# battery_interface.net
KiCad netlist of a schematic drawn in Altium Designer
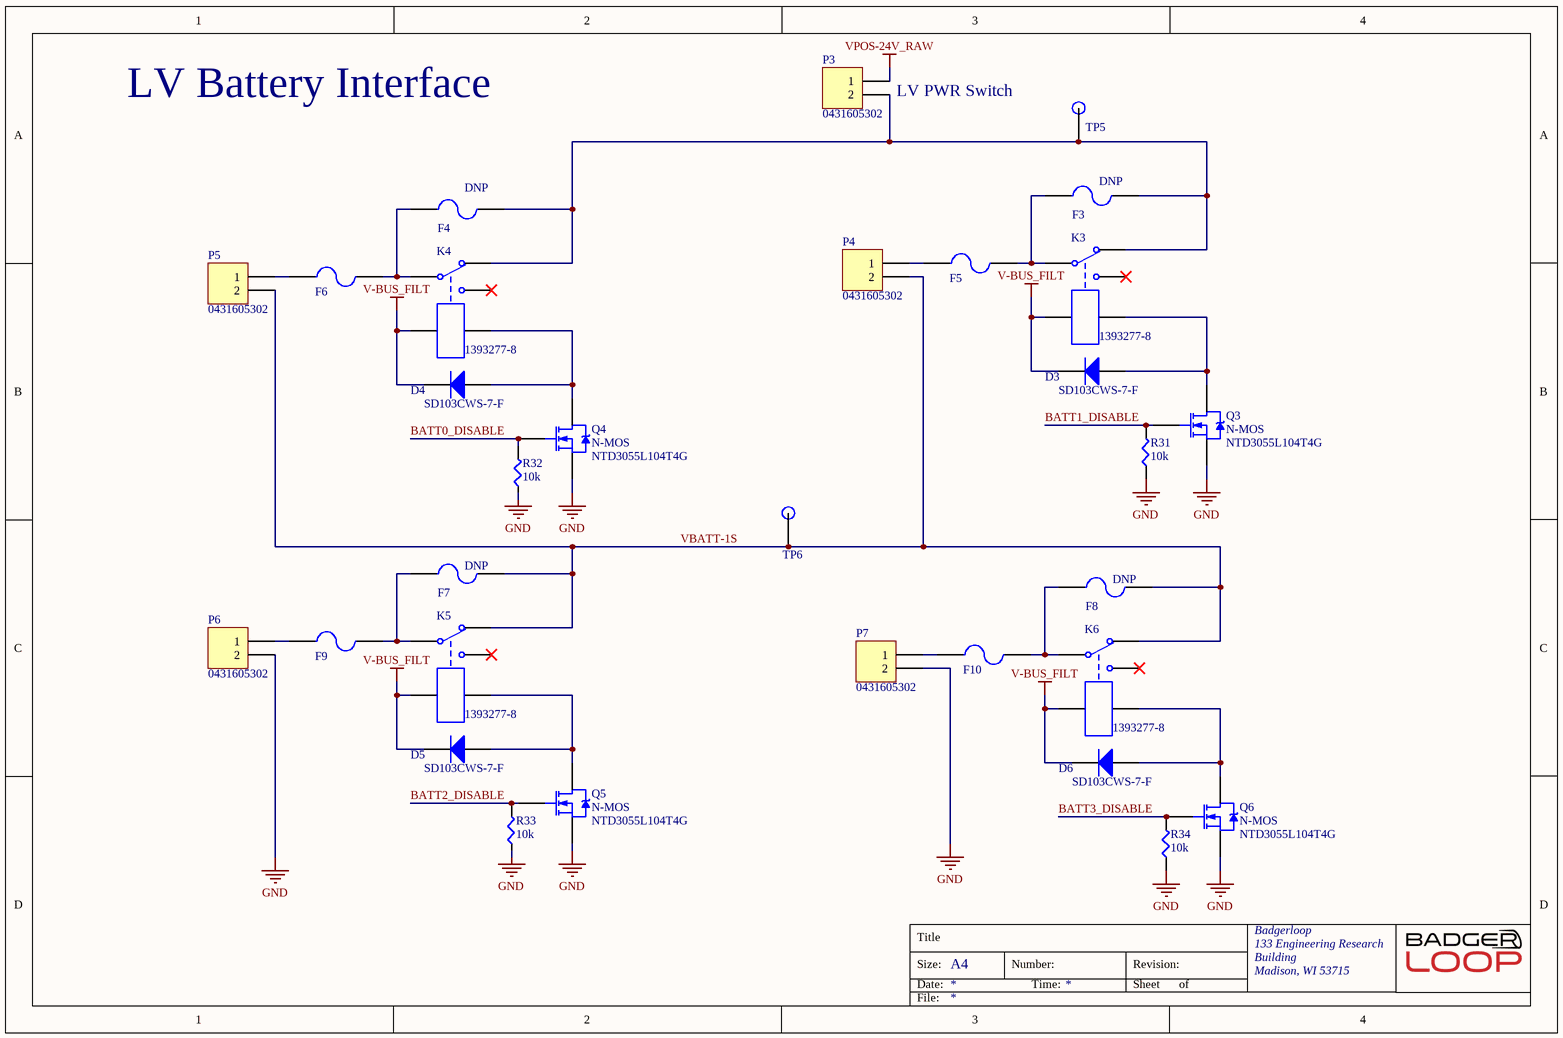
[diagram p0: battery_interface.SchDoc]

(export (version "E")
  (design (tool "Eeschema 10.0.6"))
  (components
    (comp (ref "D3")
      (value "Diode General Purpose_2")
      (footprint "SODFL250X110-2N")
      (description "DIODE GEN PURP 20V 350MA SOD323")
      (fields
        (field (name "MANUFACTURER") "Diodes Incorporated")
        (field (name "MANUFACTURER P/N") "SD103CWS-7-F")
      )
      (libsource (lib "misc") (part "Diode General Purpose_2"))
    )
    (comp (ref "D4")
      (value "Diode General Purpose_2")
      (footprint "SODFL250X110-2N")
      (description "DIODE GEN PURP 20V 350MA SOD323")
      (fields
        (field (name "MANUFACTURER") "Diodes Incorporated")
        (field (name "MANUFACTURER P/N") "SD103CWS-7-F")
      )
      (libsource (lib "misc") (part "Diode General Purpose_2"))
    )
    (comp (ref "D5")
      (value "Diode General Purpose_2")
      (footprint "SODFL250X110-2N")
      (description "DIODE GEN PURP 20V 350MA SOD323")
      (fields
        (field (name "MANUFACTURER") "Diodes Incorporated")
        (field (name "MANUFACTURER P/N") "SD103CWS-7-F")
      )
      (libsource (lib "misc") (part "Diode General Purpose_2"))
    )
    (comp (ref "D6")
      (value "Diode General Purpose_2")
      (footprint "SODFL250X110-2N")
      (description "DIODE GEN PURP 20V 350MA SOD323")
      (fields
        (field (name "MANUFACTURER") "Diodes Incorporated")
        (field (name "MANUFACTURER P/N") "SD103CWS-7-F")
      )
      (libsource (lib "misc") (part "Diode General Purpose_2"))
    )
    (comp (ref "F3")
      (value "3568")
      (footprint "Fuse Holder 30A 500V 1 Circuit Blade Through Hole")
      (description "FUSE HOLDER MINI AUTO PC")
      (fields
        (field (name "MANUFACTURER") "Keystone Electronics")
        (field (name "VOLTAGE") "500V")
        (field (name "DNP") "DNP")
      )
      (libsource (lib "misc") (part "3568"))
    )
    (comp (ref "F4")
      (value "3568")
      (footprint "Fuse Holder 30A 500V 1 Circuit Blade Through Hole")
      (description "FUSE HOLDER MINI AUTO PC")
      (fields
        (field (name "MANUFACTURER") "Keystone Electronics")
        (field (name "VOLTAGE") "500V")
        (field (name "DNP") "DNP")
      )
      (libsource (lib "misc") (part "3568"))
    )
    (comp (ref "F5")
      (value "3568")
      (footprint "Fuse Holder 30A 500V 1 Circuit Blade Through Hole")
      (description "FUSE HOLDER MINI AUTO PC")
      (fields (field (name "MANUFACTURER") "Keystone Electronics") (field (name "VOLTAGE") "500V"))
      (libsource (lib "misc") (part "3568"))
    )
    (comp (ref "F6")
      (value "3568")
      (footprint "Fuse Holder 30A 500V 1 Circuit Blade Through Hole")
      (description "FUSE HOLDER MINI AUTO PC")
      (fields (field (name "MANUFACTURER") "Keystone Electronics") (field (name "VOLTAGE") "500V"))
      (libsource (lib "misc") (part "3568"))
    )
    (comp (ref "F7")
      (value "3568")
      (footprint "Fuse Holder 30A 500V 1 Circuit Blade Through Hole")
      (description "FUSE HOLDER MINI AUTO PC")
      (fields
        (field (name "MANUFACTURER") "Keystone Electronics")
        (field (name "VOLTAGE") "500V")
        (field (name "DNP") "DNP")
      )
      (libsource (lib "misc") (part "3568"))
    )
    (comp (ref "F8")
      (value "3568")
      (footprint "Fuse Holder 30A 500V 1 Circuit Blade Through Hole")
      (description "FUSE HOLDER MINI AUTO PC")
      (fields
        (field (name "MANUFACTURER") "Keystone Electronics")
        (field (name "VOLTAGE") "500V")
        (field (name "DNP") "DNP")
      )
      (libsource (lib "misc") (part "3568"))
    )
    (comp (ref "F9")
      (value "3568")
      (footprint "Fuse Holder 30A 500V 1 Circuit Blade Through Hole")
      (description "FUSE HOLDER MINI AUTO PC")
      (fields (field (name "MANUFACTURER") "Keystone Electronics") (field (name "VOLTAGE") "500V"))
      (libsource (lib "misc") (part "3568"))
    )
    (comp (ref "F10")
      (value "3568")
      (footprint "Fuse Holder 30A 500V 1 Circuit Blade Through Hole")
      (description "FUSE HOLDER MINI AUTO PC")
      (fields (field (name "MANUFACTURER") "Keystone Electronics") (field (name "VOLTAGE") "500V"))
      (libsource (lib "misc") (part "3568"))
    )
    (comp (ref "K3")
      (value "1393277-8")
      (footprint "RELAY AUTOMOTIVE SPDT 45A 24V - duplicate")
      (description "RELAY AUTOMOTIVE SPDT 45A 24V")
      (fields (field (name "MANUFACTURER") "TE Connectivity"))
      (libsource (lib "misc") (part "1393277-8"))
    )
    (comp (ref "K4")
      (value "1393277-8")
      (footprint "RELAY AUTOMOTIVE SPDT 45A 24V - duplicate")
      (description "RELAY AUTOMOTIVE SPDT 45A 24V")
      (fields (field (name "MANUFACTURER") "TE Connectivity"))
      (libsource (lib "misc") (part "1393277-8"))
    )
    (comp (ref "K5")
      (value "1393277-8")
      (footprint "RELAY AUTOMOTIVE SPDT 45A 24V - duplicate")
      (description "RELAY AUTOMOTIVE SPDT 45A 24V")
      (fields (field (name "MANUFACTURER") "TE Connectivity"))
      (libsource (lib "misc") (part "1393277-8"))
    )
    (comp (ref "K6")
      (value "1393277-8")
      (footprint "RELAY AUTOMOTIVE SPDT 45A 24V - duplicate")
      (description "RELAY AUTOMOTIVE SPDT 45A 24V")
      (fields (field (name "MANUFACTURER") "TE Connectivity"))
      (libsource (lib "misc") (part "1393277-8"))
    )
    (comp (ref "P3")
      (value "0431605302")
      (footprint "CONN HDR 2POS 7.50MM")
      (description "Conn Power HDR 2 POS 7.49mm Solder RA Thru-Hole 4 Terminal 1 Port Sabre™ Tray")
      (fields (field (name "MANUFACTURER") "Molex"))
      (libsource (lib "connector") (part "0431605302"))
    )
    (comp (ref "P4")
      (value "0431605302")
      (footprint "CONN HDR 2POS 7.50MM")
      (description "Conn Power HDR 2 POS 7.49mm Solder RA Thru-Hole 4 Terminal 1 Port Sabre™ Tray")
      (fields (field (name "MANUFACTURER") "Molex"))
      (libsource (lib "connector") (part "0431605302"))
    )
    (comp (ref "P5")
      (value "0431605302")
      (footprint "CONN HDR 2POS 7.50MM")
      (description "Conn Power HDR 2 POS 7.49mm Solder RA Thru-Hole 4 Terminal 1 Port Sabre™ Tray")
      (fields (field (name "MANUFACTURER") "Molex"))
      (libsource (lib "connector") (part "0431605302"))
    )
    (comp (ref "P6")
      (value "0431605302")
      (footprint "CONN HDR 2POS 7.50MM")
      (description "Conn Power HDR 2 POS 7.49mm Solder RA Thru-Hole 4 Terminal 1 Port Sabre™ Tray")
      (fields (field (name "MANUFACTURER") "Molex"))
      (libsource (lib "connector") (part "0431605302"))
    )
    (comp (ref "P7")
      (value "0431605302")
      (footprint "CONN HDR 2POS 7.50MM")
      (description "Conn Power HDR 2 POS 7.49mm Solder RA Thru-Hole 4 Terminal 1 Port Sabre™ Tray")
      (fields (field (name "MANUFACTURER") "Molex"))
      (libsource (lib "connector") (part "0431605302"))
    )
    (comp (ref "Q3")
      (value "N-MOS")
      (footprint "DPAK228P991X238-3N")
      (description "N-Channel Power MOSFET, 12 A, 60 V")
      (fields (field (name "MANUFACTURER") "ON SEMI") (field (name "MANUFACTURER P/N") "NTD3055L104T4G"))
      (libsource (lib "ic") (part "N-MOS"))
    )
    (comp (ref "Q4")
      (value "N-MOS")
      (footprint "DPAK228P991X238-3N")
      (description "N-Channel Power MOSFET, 12 A, 60 V")
      (fields (field (name "MANUFACTURER") "ON SEMI") (field (name "MANUFACTURER P/N") "NTD3055L104T4G"))
      (libsource (lib "ic") (part "N-MOS"))
    )
    (comp (ref "Q5")
      (value "N-MOS")
      (footprint "DPAK228P991X238-3N")
      (description "N-Channel Power MOSFET, 12 A, 60 V")
      (fields (field (name "MANUFACTURER") "ON SEMI") (field (name "MANUFACTURER P/N") "NTD3055L104T4G"))
      (libsource (lib "ic") (part "N-MOS"))
    )
    (comp (ref "Q6")
      (value "N-MOS")
      (footprint "DPAK228P991X238-3N")
      (description "N-Channel Power MOSFET, 12 A, 60 V")
      (fields (field (name "MANUFACTURER") "ON SEMI") (field (name "MANUFACTURER P/N") "NTD3055L104T4G"))
      (libsource (lib "ic") (part "N-MOS"))
    )
    (comp (ref "R31")
      (value "10k")
      (footprint "SMD-0805-RES")
      (description "RES SMD 10K OHM 5% 1/2W 0805")
      (fields (field (name "PART NUMBER") "ERJ-P06J103V") (field (name "DIGI-KEY PART NUMBER") "P10KADCT-ND"))
      (libsource (lib "resistors") (part "ERJ-P06J103V"))
    )
    (comp (ref "R32")
      (value "10k")
      (footprint "SMD-0805-RES")
      (description "RES SMD 10K OHM 5% 1/2W 0805")
      (fields (field (name "PART NUMBER") "ERJ-P06J103V") (field (name "DIGI-KEY PART NUMBER") "P10KADCT-ND"))
      (libsource (lib "resistors") (part "ERJ-P06J103V"))
    )
    (comp (ref "R33")
      (value "10k")
      (footprint "SMD-0805-RES")
      (description "RES SMD 10K OHM 5% 1/2W 0805")
      (fields (field (name "PART NUMBER") "ERJ-P06J103V") (field (name "DIGI-KEY PART NUMBER") "P10KADCT-ND"))
      (libsource (lib "resistors") (part "ERJ-P06J103V"))
    )
    (comp (ref "R34")
      (value "10k")
      (footprint "SMD-0805-RES")
      (description "RES SMD 10K OHM 5% 1/2W 0805")
      (fields (field (name "PART NUMBER") "ERJ-P06J103V") (field (name "DIGI-KEY PART NUMBER") "P10KADCT-ND"))
      (libsource (lib "resistors") (part "ERJ-P06J103V"))
    )
    (comp (ref "TP5")
      (value "TP")
      (footprint "Test Point")
      (description "SMD TEST POINT")
      (libsource (lib "misc") (part "TP"))
    )
    (comp (ref "TP6")
      (value "TP")
      (footprint "Test Point")
      (description "SMD TEST POINT")
      (libsource (lib "misc") (part "TP"))
    )
  )
  (nets
    (net (code "1") (name "/BATT0_DISABLE") (class "Default")
      (node (ref "Q4") (pin "1") (pinfunction "G_1") (pintype "passive"))
      (node (ref "R32") (pin "2") (pinfunction "2_2") (pintype "passive"))
    )
    (net (code "2") (name "/BATT1_DISABLE") (class "Default")
      (node (ref "Q3") (pin "1") (pinfunction "G_1") (pintype "passive"))
      (node (ref "R31") (pin "2") (pinfunction "2_2") (pintype "passive"))
    )
    (net (code "3") (name "/BATT2_DISABLE") (class "Default")
      (node (ref "Q5") (pin "1") (pinfunction "G_1") (pintype "passive"))
      (node (ref "R33") (pin "2") (pinfunction "2_2") (pintype "passive"))
    )
    (net (code "4") (name "/BATT3_DISABLE") (class "Default")
      (node (ref "Q6") (pin "1") (pinfunction "G_1") (pintype "passive"))
      (node (ref "R34") (pin "2") (pinfunction "2_2") (pintype "passive"))
    )
    (net (code "5") (name "/VBATT-1S") (class "Default")
      (node (ref "F7") (pin "2") (pinfunction "2_2") (pintype "passive"))
      (node (ref "F8") (pin "2") (pinfunction "2_2") (pintype "passive"))
      (node (ref "K5") (pin "3") (pinfunction "3_3") (pintype "passive"))
      (node (ref "K6") (pin "3") (pinfunction "3_3") (pintype "passive"))
      (node (ref "P4") (pin "2") (pinfunction "2_2") (pintype "passive"))
      (node (ref "P5") (pin "2") (pinfunction "2_2") (pintype "passive"))
      (node (ref "TP6") (pin "1") (pinfunction "1_1") (pintype "passive"))
    )
    (net (code "6") (name "GND") (class "Default")
      (node (ref "P6") (pin "2") (pinfunction "2_2") (pintype "passive"))
      (node (ref "P7") (pin "2") (pinfunction "2_2") (pintype "passive"))
      (node (ref "Q3") (pin "3") (pinfunction "S_3") (pintype "passive"))
      (node (ref "Q4") (pin "3") (pinfunction "S_3") (pintype "passive"))
      (node (ref "Q5") (pin "3") (pinfunction "S_3") (pintype "passive"))
      (node (ref "Q6") (pin "3") (pinfunction "S_3") (pintype "passive"))
      (node (ref "R31") (pin "1") (pinfunction "1_1") (pintype "passive"))
      (node (ref "R32") (pin "1") (pinfunction "1_1") (pintype "passive"))
      (node (ref "R33") (pin "1") (pinfunction "1_1") (pintype "passive"))
      (node (ref "R34") (pin "1") (pinfunction "1_1") (pintype "passive"))
    )
    (net (code "7") (name "Net-(D3-A)") (class "Default")
      (node (ref "D3") (pin "1") (pinfunction "A_1") (pintype "passive"))
      (node (ref "K3") (pin "2") (pinfunction "2_2") (pintype "passive"))
      (node (ref "Q3") (pin "4") (pinfunction "D_4") (pintype "passive"))
    )
    (net (code "8") (name "Net-(D4-A)") (class "Default")
      (node (ref "D4") (pin "1") (pinfunction "A_1") (pintype "passive"))
      (node (ref "K4") (pin "2") (pinfunction "2_2") (pintype "passive"))
      (node (ref "Q4") (pin "4") (pinfunction "D_4") (pintype "passive"))
    )
    (net (code "9") (name "Net-(D5-A)") (class "Default")
      (node (ref "D5") (pin "1") (pinfunction "A_1") (pintype "passive"))
      (node (ref "K5") (pin "2") (pinfunction "2_2") (pintype "passive"))
      (node (ref "Q5") (pin "4") (pinfunction "D_4") (pintype "passive"))
    )
    (net (code "10") (name "Net-(D6-A)") (class "Default")
      (node (ref "D6") (pin "1") (pinfunction "A_1") (pintype "passive"))
      (node (ref "K6") (pin "2") (pinfunction "2_2") (pintype "passive"))
      (node (ref "Q6") (pin "4") (pinfunction "D_4") (pintype "passive"))
    )
    (net (code "11") (name "Net-(F3-Pad1)") (class "Default")
      (node (ref "F3") (pin "1") (pinfunction "1_1") (pintype "passive"))
      (node (ref "F5") (pin "2") (pinfunction "2_2") (pintype "passive"))
      (node (ref "K3") (pin "4") (pinfunction "4_4") (pintype "passive"))
    )
    (net (code "12") (name "Net-(F3-Pad2)") (class "Default")
      (node (ref "F3") (pin "2") (pinfunction "2_2") (pintype "passive"))
      (node (ref "F4") (pin "2") (pinfunction "2_2") (pintype "passive"))
      (node (ref "K3") (pin "3") (pinfunction "3_3") (pintype "passive"))
      (node (ref "K4") (pin "3") (pinfunction "3_3") (pintype "passive"))
      (node (ref "P3") (pin "2") (pinfunction "2_2") (pintype "passive"))
      (node (ref "TP5") (pin "1") (pinfunction "1_1") (pintype "passive"))
    )
    (net (code "13") (name "Net-(F4-Pad1)") (class "Default")
      (node (ref "F4") (pin "1") (pinfunction "1_1") (pintype "passive"))
      (node (ref "F6") (pin "2") (pinfunction "2_2") (pintype "passive"))
      (node (ref "K4") (pin "4") (pinfunction "4_4") (pintype "passive"))
    )
    (net (code "14") (name "Net-(F5-Pad1)") (class "Default")
      (node (ref "F5") (pin "1") (pinfunction "1_1") (pintype "passive"))
      (node (ref "P4") (pin "1") (pinfunction "1_1") (pintype "passive"))
    )
    (net (code "15") (name "Net-(F6-Pad1)") (class "Default")
      (node (ref "F6") (pin "1") (pinfunction "1_1") (pintype "passive"))
      (node (ref "P5") (pin "1") (pinfunction "1_1") (pintype "passive"))
    )
    (net (code "16") (name "Net-(F7-Pad1)") (class "Default")
      (node (ref "F7") (pin "1") (pinfunction "1_1") (pintype "passive"))
      (node (ref "F9") (pin "2") (pinfunction "2_2") (pintype "passive"))
      (node (ref "K5") (pin "4") (pinfunction "4_4") (pintype "passive"))
    )
    (net (code "17") (name "Net-(F9-Pad1)") (class "Default")
      (node (ref "F9") (pin "1") (pinfunction "1_1") (pintype "passive"))
      (node (ref "P6") (pin "1") (pinfunction "1_1") (pintype "passive"))
    )
    (net (code "18") (name "Net-(F10-Pad1)") (class "Default")
      (node (ref "F10") (pin "1") (pinfunction "1_1") (pintype "passive"))
      (node (ref "P7") (pin "1") (pinfunction "1_1") (pintype "passive"))
    )
    (net (code "19") (name "Net-(F10-Pad2)") (class "Default")
      (node (ref "F10") (pin "2") (pinfunction "2_2") (pintype "passive"))
      (node (ref "F8") (pin "1") (pinfunction "1_1") (pintype "passive"))
      (node (ref "K6") (pin "4") (pinfunction "4_4") (pintype "passive"))
    )
    (net (code "20") (name "V-BUS_FILT") (class "Default")
      (node (ref "D3") (pin "2") (pinfunction "K_2") (pintype "passive"))
      (node (ref "D4") (pin "2") (pinfunction "K_2") (pintype "passive"))
      (node (ref "D5") (pin "2") (pinfunction "K_2") (pintype "passive"))
      (node (ref "D6") (pin "2") (pinfunction "K_2") (pintype "passive"))
      (node (ref "K3") (pin "1") (pinfunction "1_1") (pintype "passive"))
      (node (ref "K4") (pin "1") (pinfunction "1_1") (pintype "passive"))
      (node (ref "K5") (pin "1") (pinfunction "1_1") (pintype "passive"))
      (node (ref "K6") (pin "1") (pinfunction "1_1") (pintype "passive"))
    )
    (net (code "21") (name "VPOS-24V_RAW") (class "Default")
      (node (ref "P3") (pin "1") (pinfunction "1_1") (pintype "passive"))
    )
    (net (code "22") (name "unconnected-(K3-Pad5)") (class "Default")
      (node (ref "K3") (pin "5") (pinfunction "5_5") (pintype "passive+no_connect"))
    )
    (net (code "23") (name "unconnected-(K4-Pad5)") (class "Default")
      (node (ref "K4") (pin "5") (pinfunction "5_5") (pintype "passive+no_connect"))
    )
    (net (code "24") (name "unconnected-(K5-Pad5)") (class "Default")
      (node (ref "K5") (pin "5") (pinfunction "5_5") (pintype "passive+no_connect"))
    )
    (net (code "25") (name "unconnected-(K6-Pad5)") (class "Default")
      (node (ref "K6") (pin "5") (pinfunction "5_5") (pintype "passive+no_connect"))
    )
  )
)
